# Lsensor.net
KiCad netlist of a schematic drawn in EAGLE
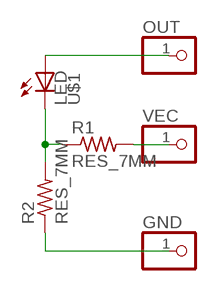
[diagram p0: schematic, sheet 1]

(export (version "E")
  (design (tool "Eeschema 10.0.6"))
  (components
    (comp (ref "GND")
      (value "PINHD-1X1")
      (footprint "eagle-import:1X01")
      (libsource (lib "eagle-import") (part "PINHD-1X1"))
    )
    (comp (ref "OUT")
      (value "PINHD-1X1")
      (footprint "eagle-import:1X01")
      (libsource (lib "eagle-import") (part "PINHD-1X1"))
    )
    (comp (ref "R1")
      (value "RES_7MM")
      (footprint "eagle-import:0204_7")
      (libsource (lib "eagle-import") (part "RES_7MM"))
    )
    (comp (ref "R2")
      (value "RES_7MM")
      (footprint "eagle-import:0204_7")
      (libsource (lib "eagle-import") (part "RES_7MM"))
    )
    (comp (ref "U$1")
      (value "LED")
      (footprint "eagle-import:5MM")
      (libsource (lib "eagle-import") (part "LED"))
    )
    (comp (ref "VEC")
      (value "PINHD-1X1")
      (footprint "eagle-import:1X01")
      (libsource (lib "eagle-import") (part "PINHD-1X1"))
    )
  )
  (nets
    (net (code "1") (name "Net-(GND-Pad1)") (class "Default")
      (node (ref "GND") (pin "1") (pinfunction "1_1") (pintype "passive"))
      (node (ref "R2") (pin "1") (pinfunction "1_1") (pintype "passive"))
    )
    (net (code "2") (name "Net-(R1-Pad2)") (class "Default")
      (node (ref "R1") (pin "2") (pinfunction "2_2") (pintype "passive"))
      (node (ref "VEC") (pin "1") (pinfunction "1_1") (pintype "passive"))
    )
    (net (code "3") (name "Net-(U$1-A)") (class "Default")
      (node (ref "OUT") (pin "1") (pinfunction "1_1") (pintype "passive"))
      (node (ref "U$1") (pin "IN") (pinfunction "A_IN") (pintype "passive"))
    )
    (net (code "4") (name "Net-(U$1-C)") (class "Default")
      (node (ref "R1") (pin "1") (pinfunction "1_1") (pintype "passive"))
      (node (ref "R2") (pin "2") (pinfunction "2_2") (pintype "passive"))
      (node (ref "U$1") (pin "OUT") (pinfunction "C_OUT") (pintype "passive"))
    )
  )
)
